# rtu03.net
KiCad netlist of a schematic drawn in EAGLE
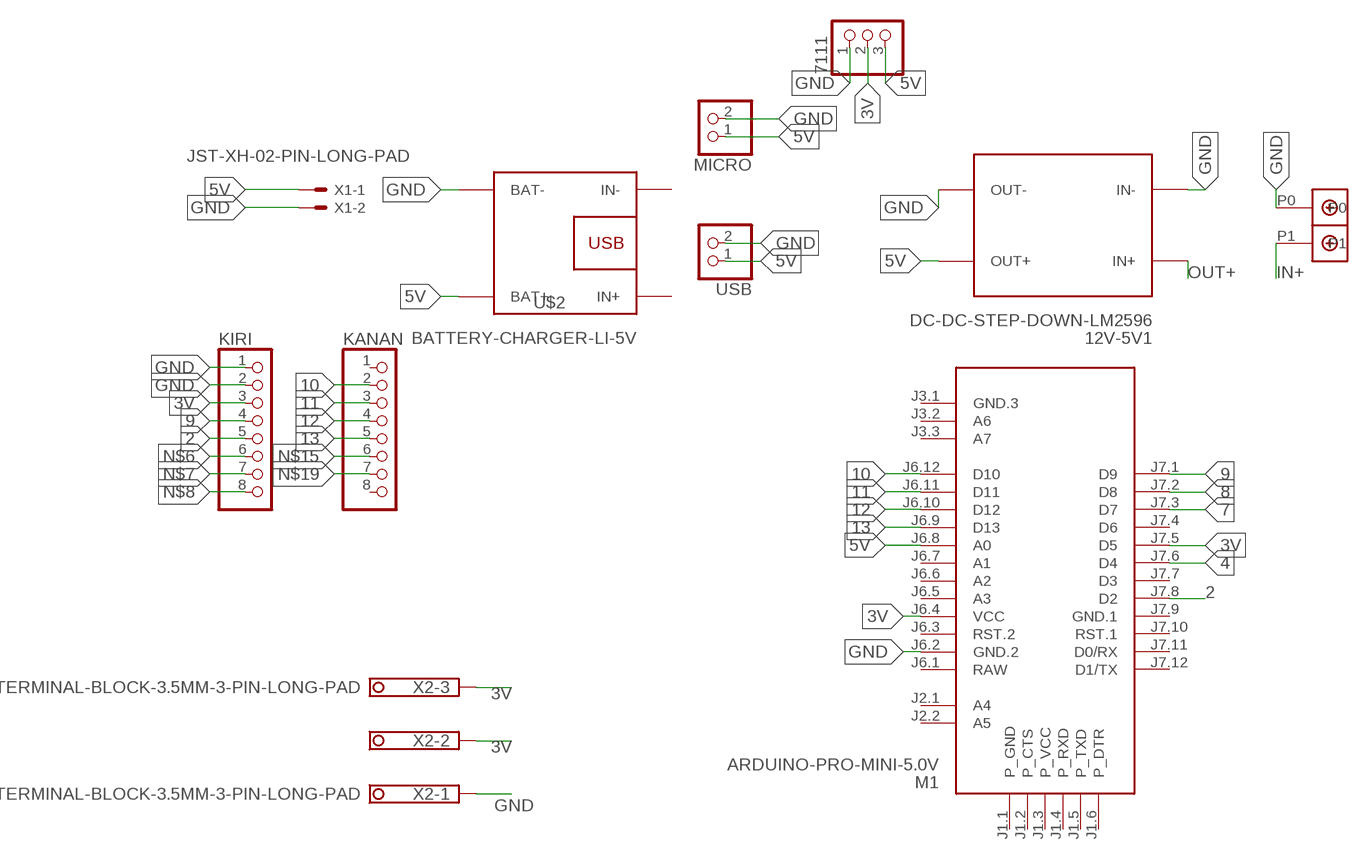
[diagram p0: schematic, sheet 1]

(export (version "E")
  (design (tool "Eeschema 10.0.6"))
  (components
    (comp (ref "12V-5V1")
      (value "DC-DC-STEP-DOWN-LM2596")
      (footprint "eagle-import:DC-DC-STEP-DOWN-LM2596")
      (libsource (lib "eagle-import") (part "DC-DC-STEP-DOWN-LM2596"))
    )
    (comp (ref "7111")
      (value "PINHD-1X3")
      (footprint "eagle-import:1X03")
      (libsource (lib "eagle-import") (part "PINHD-1X3"))
    )
    (comp (ref "KANAN")
      (value "PINHD-1X8")
      (footprint "eagle-import:1X08")
      (libsource (lib "eagle-import") (part "PINHD-1X8"))
    )
    (comp (ref "KIRI")
      (value "PINHD-1X8")
      (footprint "eagle-import:1X08")
      (libsource (lib "eagle-import") (part "PINHD-1X8"))
    )
    (comp (ref "M1")
      (value "ARDUINO-PRO-MINI-5.0V")
      (footprint "eagle-import:ARDUINO-PRO-MINI")
      (libsource (lib "eagle-import") (part "ARDUINO-PRO-MINI-5.0V"))
    )
    (comp (ref "MICRO")
      (value "PINHD-1X2")
      (footprint "eagle-import:1X02")
      (libsource (lib "eagle-import") (part "PINHD-1X2"))
    )
    (comp (ref "U$1")
      (value "DBCONN-1X2")
      (footprint "eagle-import:DBCONN-1X2")
      (libsource (lib "eagle-import") (part "DBCONN-1X2"))
    )
    (comp (ref "U$2")
      (value "BATTERY-CHARGER-LI-5V")
      (footprint "eagle-import:BATTERY-CHARGER-LI-5V")
      (libsource (lib "eagle-import") (part "BATTERY-CHARGER-LI-5V"))
    )
    (comp (ref "USB")
      (value "PINHD-1X2")
      (footprint "eagle-import:1X02")
      (libsource (lib "eagle-import") (part "PINHD-1X2"))
    )
    (comp (ref "X1")
      (value "JST-XH-02-PIN-LONG-PAD")
      (footprint "eagle-import:JST-XH-02-PACKAGE-LONG-PAD")
      (libsource (lib "eagle-import") (part "JST-XH-02-PIN-LONG-PAD"))
    )
    (comp (ref "X2")
      (value "TERMINAL-BLOCK-3.5MM-3-PIN-LONG-PAD")
      (footprint "eagle-import:TERMINAL-BLOCK-3-PIN-3.5MM-LONG-PAD")
      (libsource (lib "eagle-import") (part "TERMINAL-BLOCK-3.5MM-3-PIN-LONG-PAD"))
    )
  )
  (nets
    (net (code "1") (name "/GND.1") (class "Default")
      (node (ref "M1") (pin "J7.9") (pinfunction "GND.1_J7.9") (pintype "power_in"))
    )
    (net (code "2") (name "/IN+") (class "Default")
      (node (ref "U$1") (pin "P1") (pinfunction "P1_P1") (pintype "bidirectional"))
    )
    (net (code "3") (name "/OUT+") (class "Default")
      (node (ref "12V-5V1") (pin "IN+") (pinfunction "IN+_IN+") (pintype "bidirectional"))
    )
    (net (code "4") (name "/RAW") (class "Default")
      (node (ref "M1") (pin "J6.1") (pinfunction "RAW_J6.1") (pintype "power_in"))
    )
    (net (code "5") (name "2") (class "Default")
      (node (ref "KIRI") (pin "5") (pinfunction "5_5") (pintype "passive"))
      (node (ref "M1") (pin "J7.8") (pinfunction "D2_J7.8") (pintype "bidirectional"))
    )
    (net (code "6") (name "3V") (class "Default")
      (node (ref "7111") (pin "2") (pinfunction "2_2") (pintype "passive"))
      (node (ref "KIRI") (pin "3") (pinfunction "3_3") (pintype "passive"))
      (node (ref "M1") (pin "J6.4") (pinfunction "VCC_J6.4") (pintype "power_in"))
      (node (ref "M1") (pin "J7.5") (pinfunction "D5_J7.5") (pintype "bidirectional"))
      (node (ref "X2") (pin "2") (pinfunction "K_2") (pintype "passive"))
      (node (ref "X2") (pin "3") (pinfunction "K_3") (pintype "passive"))
    )
    (net (code "7") (name "4") (class "Default")
      (node (ref "M1") (pin "J7.6") (pinfunction "D4_J7.6") (pintype "bidirectional"))
    )
    (net (code "8") (name "5V") (class "Default")
      (node (ref "12V-5V1") (pin "OUT+") (pinfunction "OUT+_OUT+") (pintype "bidirectional"))
      (node (ref "7111") (pin "3") (pinfunction "3_3") (pintype "passive"))
      (node (ref "M1") (pin "J6.8") (pinfunction "A0_J6.8") (pintype "bidirectional"))
      (node (ref "MICRO") (pin "1") (pinfunction "1_1") (pintype "passive"))
      (node (ref "U$2") (pin "BAT+") (pinfunction "BAT+_BAT+") (pintype "bidirectional"))
      (node (ref "USB") (pin "1") (pinfunction "1_1") (pintype "passive"))
      (node (ref "X1") (pin "1") (pinfunction "S_1") (pintype "passive"))
    )
    (net (code "9") (name "7") (class "Default")
      (node (ref "M1") (pin "J7.3") (pinfunction "D7_J7.3") (pintype "bidirectional"))
    )
    (net (code "10") (name "8") (class "Default")
      (node (ref "M1") (pin "J7.2") (pinfunction "D8_J7.2") (pintype "bidirectional"))
    )
    (net (code "11") (name "9") (class "Default")
      (node (ref "KIRI") (pin "4") (pinfunction "4_4") (pintype "passive"))
      (node (ref "M1") (pin "J7.1") (pinfunction "D9_J7.1") (pintype "bidirectional"))
    )
    (net (code "12") (name "10") (class "Default")
      (node (ref "KANAN") (pin "2") (pinfunction "2_2") (pintype "passive"))
      (node (ref "M1") (pin "J6.12") (pinfunction "D10_J6.12") (pintype "bidirectional"))
    )
    (net (code "13") (name "11") (class "Default")
      (node (ref "KANAN") (pin "3") (pinfunction "3_3") (pintype "passive"))
      (node (ref "M1") (pin "J6.11") (pinfunction "D11_J6.11") (pintype "bidirectional"))
    )
    (net (code "14") (name "12") (class "Default")
      (node (ref "KANAN") (pin "4") (pinfunction "4_4") (pintype "passive"))
      (node (ref "M1") (pin "J6.10") (pinfunction "D12_J6.10") (pintype "bidirectional"))
    )
    (net (code "15") (name "13") (class "Default")
      (node (ref "KANAN") (pin "5") (pinfunction "5_5") (pintype "passive"))
      (node (ref "M1") (pin "J6.9") (pinfunction "D13_J6.9") (pintype "bidirectional"))
    )
    (net (code "16") (name "GND") (class "Default")
      (node (ref "12V-5V1") (pin "IN-") (pinfunction "IN-_IN-") (pintype "bidirectional"))
      (node (ref "12V-5V1") (pin "OUT-") (pinfunction "OUT-_OUT-") (pintype "bidirectional"))
      (node (ref "7111") (pin "1") (pinfunction "1_1") (pintype "passive"))
      (node (ref "KIRI") (pin "1") (pinfunction "1_1") (pintype "passive"))
      (node (ref "KIRI") (pin "2") (pinfunction "2_2") (pintype "passive"))
      (node (ref "M1") (pin "J6.2") (pinfunction "GND.2_J6.2") (pintype "power_in"))
      (node (ref "MICRO") (pin "2") (pinfunction "2_2") (pintype "passive"))
      (node (ref "U$1") (pin "P0") (pinfunction "P0_P0") (pintype "bidirectional"))
      (node (ref "U$2") (pin "BAT-") (pinfunction "BAT-_BAT-") (pintype "bidirectional"))
      (node (ref "USB") (pin "2") (pinfunction "2_2") (pintype "passive"))
      (node (ref "X1") (pin "2") (pinfunction "S_2") (pintype "passive"))
      (node (ref "X2") (pin "1") (pinfunction "K_1") (pintype "passive"))
    )
    (net (code "17") (name "N$6") (class "Default")
      (node (ref "KIRI") (pin "6") (pinfunction "6_6") (pintype "passive"))
    )
    (net (code "18") (name "N$7") (class "Default")
      (node (ref "KIRI") (pin "7") (pinfunction "7_7") (pintype "passive"))
    )
    (net (code "19") (name "N$8") (class "Default")
      (node (ref "KIRI") (pin "8") (pinfunction "8_8") (pintype "passive"))
    )
    (net (code "20") (name "N$15") (class "Default")
      (node (ref "KANAN") (pin "6") (pinfunction "6_6") (pintype "passive"))
    )
    (net (code "21") (name "N$19") (class "Default")
      (node (ref "KANAN") (pin "7") (pinfunction "7_7") (pintype "passive"))
    )
    (net (code "22") (name "unconnected-(KANAN-Pad1)") (class "Default")
      (node (ref "KANAN") (pin "1") (pinfunction "1_1") (pintype "passive"))
    )
    (net (code "23") (name "unconnected-(KANAN-Pad8)") (class "Default")
      (node (ref "KANAN") (pin "8") (pinfunction "8_8") (pintype "passive"))
    )
    (net (code "24") (name "unconnected-(M1-A1-PadJ6.7)") (class "Default")
      (node (ref "M1") (pin "J6.7") (pinfunction "A1_J6.7") (pintype "bidirectional"))
    )
    (net (code "25") (name "unconnected-(M1-A2-PadJ6.6)") (class "Default")
      (node (ref "M1") (pin "J6.6") (pinfunction "A2_J6.6") (pintype "bidirectional"))
    )
    (net (code "26") (name "unconnected-(M1-A3-PadJ6.5)") (class "Default")
      (node (ref "M1") (pin "J6.5") (pinfunction "A3_J6.5") (pintype "bidirectional"))
    )
    (net (code "27") (name "unconnected-(M1-A4-PadJ2.1)") (class "Default")
      (node (ref "M1") (pin "J2.1") (pinfunction "A4_J2.1") (pintype "bidirectional"))
    )
    (net (code "28") (name "unconnected-(M1-A5-PadJ2.2)") (class "Default")
      (node (ref "M1") (pin "J2.2") (pinfunction "A5_J2.2") (pintype "bidirectional"))
    )
    (net (code "29") (name "unconnected-(M1-A6-PadJ3.2)") (class "Default")
      (node (ref "M1") (pin "J3.2") (pinfunction "A6_J3.2") (pintype "bidirectional"))
    )
    (net (code "30") (name "unconnected-(M1-A7-PadJ3.3)") (class "Default")
      (node (ref "M1") (pin "J3.3") (pinfunction "A7_J3.3") (pintype "bidirectional"))
    )
    (net (code "31") (name "unconnected-(M1-D0{slash}RX-PadJ7.11)") (class "Default")
      (node (ref "M1") (pin "J7.11") (pinfunction "D0/RX_J7.11") (pintype "bidirectional"))
    )
    (net (code "32") (name "unconnected-(M1-D1{slash}TX-PadJ7.12)") (class "Default")
      (node (ref "M1") (pin "J7.12") (pinfunction "D1/TX_J7.12") (pintype "bidirectional"))
    )
    (net (code "33") (name "unconnected-(M1-D3-PadJ7.7)") (class "Default")
      (node (ref "M1") (pin "J7.7") (pinfunction "D3_J7.7") (pintype "bidirectional"))
    )
    (net (code "34") (name "unconnected-(M1-D6-PadJ7.4)") (class "Default")
      (node (ref "M1") (pin "J7.4") (pinfunction "D6_J7.4") (pintype "bidirectional"))
    )
    (net (code "35") (name "unconnected-(M1-GND.3-PadJ3.1)") (class "Default")
      (node (ref "M1") (pin "J3.1") (pinfunction "GND.3_J3.1") (pintype "bidirectional"))
    )
    (net (code "36") (name "unconnected-(M1-P_CTS-PadJ1.2)") (class "Default")
      (node (ref "M1") (pin "J1.2") (pinfunction "P_CTS_J1.2") (pintype "bidirectional"))
    )
    (net (code "37") (name "unconnected-(M1-P_DTR-PadJ1.6)") (class "Default")
      (node (ref "M1") (pin "J1.6") (pinfunction "P_DTR_J1.6") (pintype "bidirectional"))
    )
    (net (code "38") (name "unconnected-(M1-P_GND-PadJ1.1)") (class "Default")
      (node (ref "M1") (pin "J1.1") (pinfunction "P_GND_J1.1") (pintype "bidirectional"))
    )
    (net (code "39") (name "unconnected-(M1-P_RXD-PadJ1.4)") (class "Default")
      (node (ref "M1") (pin "J1.4") (pinfunction "P_RXD_J1.4") (pintype "bidirectional"))
    )
    (net (code "40") (name "unconnected-(M1-P_TXD-PadJ1.5)") (class "Default")
      (node (ref "M1") (pin "J1.5") (pinfunction "P_TXD_J1.5") (pintype "bidirectional"))
    )
    (net (code "41") (name "unconnected-(M1-P_VCC-PadJ1.3)") (class "Default")
      (node (ref "M1") (pin "J1.3") (pinfunction "P_VCC_J1.3") (pintype "bidirectional"))
    )
    (net (code "42") (name "unconnected-(M1-RST.1-PadJ7.10)") (class "Default")
      (node (ref "M1") (pin "J7.10") (pinfunction "RST.1_J7.10") (pintype "bidirectional"))
    )
    (net (code "43") (name "unconnected-(M1-RST.2-PadJ6.3)") (class "Default")
      (node (ref "M1") (pin "J6.3") (pinfunction "RST.2_J6.3") (pintype "bidirectional"))
    )
    (net (code "44") (name "unconnected-(U$2-PadIN+)") (class "Default")
      (node (ref "U$2") (pin "IN+") (pinfunction "IN+_IN+") (pintype "bidirectional"))
    )
    (net (code "45") (name "unconnected-(U$2-PadIN-)") (class "Default")
      (node (ref "U$2") (pin "IN-") (pinfunction "IN-_IN-") (pintype "bidirectional"))
    )
  )
)
